# ProteccionesCPLD.net
KiCad netlist of a schematic drawn in Altium Designer
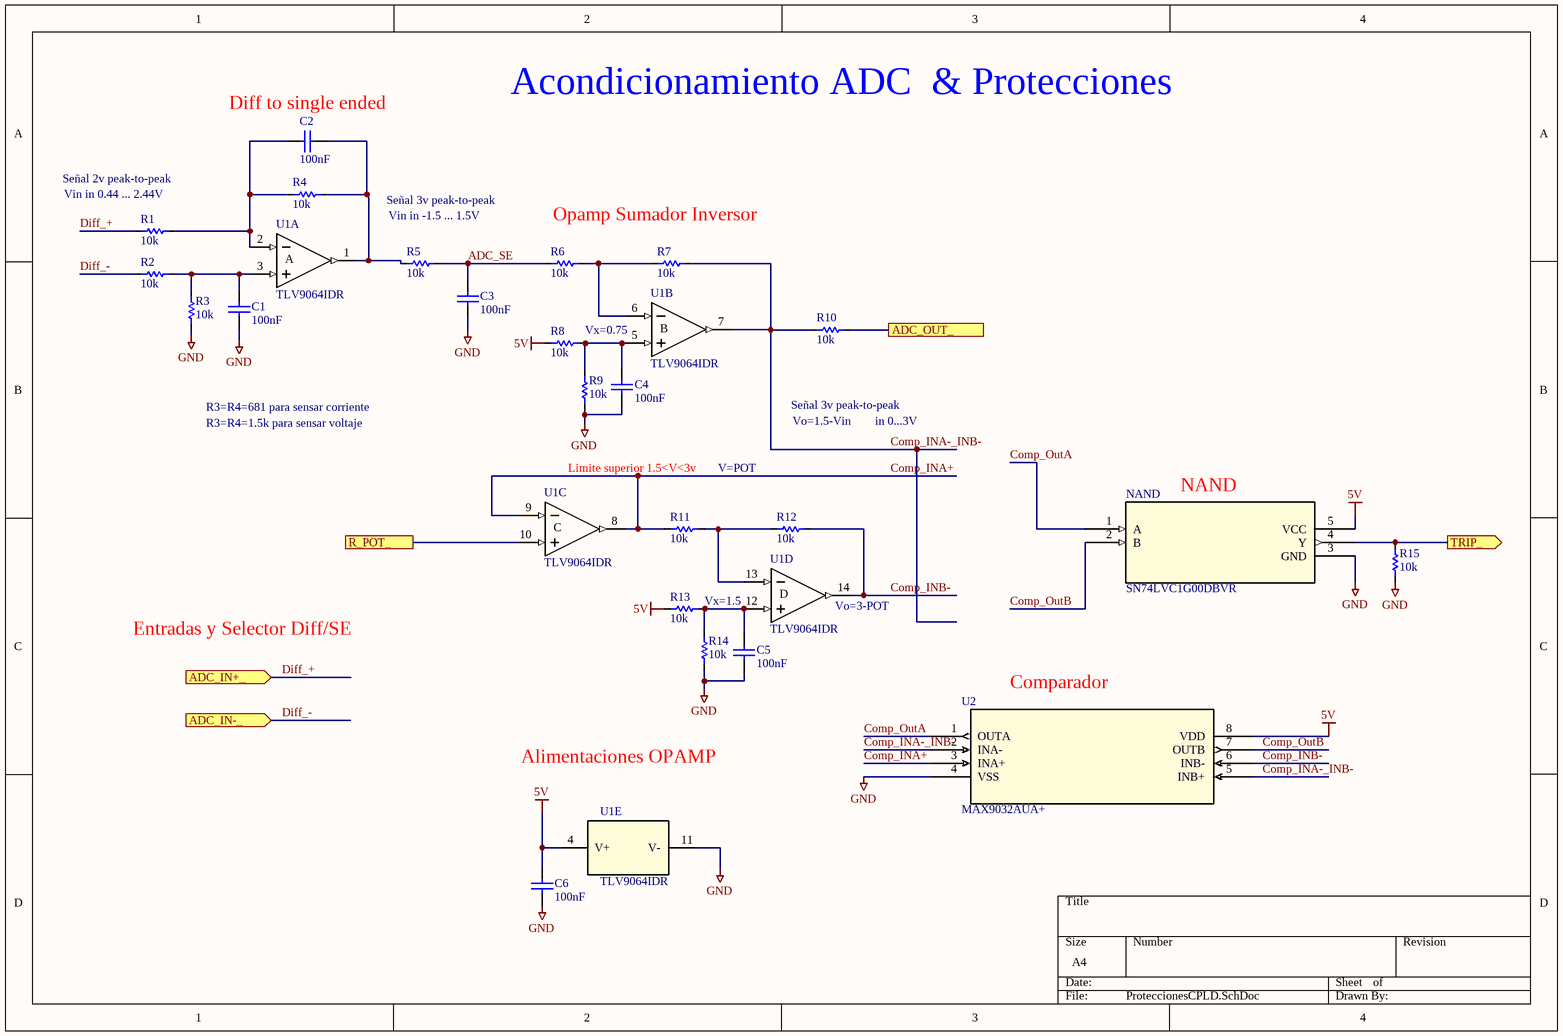
[diagram p0: ProteccionesCPLD.SchDoc]

(export (version "E")
  (design (tool "Eeschema 10.0.6"))
  (components
    (comp (ref "C1")
      (value "100nF")
      (footprint "CAP_0603")
      (description "0.1µF ±10% 50V Ceramic Capacitor X7R 0603 (1608 Metric)")
      (fields (field (name "MF") "KEMET") (field (name "CREATED") "2020_06_15_DAarancibia"))
      (libsource (lib "Schlib1") (part "Cap_0603"))
    )
    (comp (ref "C2")
      (value "100nF")
      (footprint "CAP_0603")
      (description "0.1µF ±10% 50V Ceramic Capacitor X7R 0603 (1608 Metric)")
      (fields (field (name "MF") "KEMET") (field (name "CREATED") "2020_06_15_DAarancibia"))
      (libsource (lib "Schlib1") (part "Cap_0603"))
    )
    (comp (ref "C3")
      (value "100nF")
      (footprint "CAP_0603")
      (description "0.1µF ±10% 50V Ceramic Capacitor X7R 0603 (1608 Metric)")
      (fields (field (name "MF") "KEMET") (field (name "CREATED") "2020_06_15_DAarancibia"))
      (libsource (lib "Schlib1") (part "Cap_0603"))
    )
    (comp (ref "C4")
      (value "100nF")
      (footprint "CAP_0603")
      (description "0.1µF ±10% 50V Ceramic Capacitor X7R 0603 (1608 Metric)")
      (fields (field (name "MF") "KEMET") (field (name "CREATED") "2020_06_15_DAarancibia"))
      (libsource (lib "Schlib1") (part "Cap_0603"))
    )
    (comp (ref "C5")
      (value "100nF")
      (footprint "CAP_0603")
      (description "0.1µF ±10% 50V Ceramic Capacitor X7R 0603 (1608 Metric)")
      (fields (field (name "MF") "KEMET") (field (name "CREATED") "2020_06_15_DAarancibia"))
      (libsource (lib "Schlib1") (part "Cap_0603"))
    )
    (comp (ref "C6")
      (value "100nF")
      (footprint "CAP_0603")
      (description "0.1µF ±10% 50V Ceramic Capacitor X7R 0603 (1608 Metric)")
      (fields (field (name "MF") "KEMET") (field (name "CREATED") "2020_06_15_DAarancibia"))
      (libsource (lib "Schlib1") (part "Cap_0603"))
    )
    (comp (ref "NAND")
      (value "SN74LVC1G00DBVR")
      (footprint "DBV5-M")
      (description "No Description Available")
      (libsource (lib "Schlib1") (part "SN74LVC1G00DBVR"))
    )
    (comp (ref "R1")
      (value "10k")
      (footprint "RES_0603")
      (fields
        (field (name "MF") "Panasonic Electronic Components")
        (field (name "CREATED") "2020_06_15_DAarancibia")
      )
      (libsource (lib "Schlib1") (part "Res_0603"))
    )
    (comp (ref "R2")
      (value "10k")
      (footprint "RES_0603")
      (fields
        (field (name "MF") "Panasonic Electronic Components")
        (field (name "CREATED") "2020_06_15_DAarancibia")
      )
      (libsource (lib "Schlib1") (part "Res_0603"))
    )
    (comp (ref "R3")
      (value "10k")
      (footprint "RES_0603")
      (fields
        (field (name "MF") "Panasonic Electronic Components")
        (field (name "CREATED") "2020_06_15_DAarancibia")
      )
      (libsource (lib "Schlib1") (part "Res_0603"))
    )
    (comp (ref "R4")
      (value "10k")
      (footprint "RES_0603")
      (fields
        (field (name "MF") "Panasonic Electronic Components")
        (field (name "CREATED") "2020_06_15_DAarancibia")
      )
      (libsource (lib "Schlib1") (part "Res_0603"))
    )
    (comp (ref "R5")
      (value "10k")
      (footprint "RES_0603")
      (fields
        (field (name "MF") "Panasonic Electronic Components")
        (field (name "CREATED") "2020_06_15_DAarancibia")
      )
      (libsource (lib "Schlib1") (part "Res_0603"))
    )
    (comp (ref "R6")
      (value "10k")
      (footprint "RES_0603")
      (fields
        (field (name "MF") "Panasonic Electronic Components")
        (field (name "CREATED") "2020_06_15_DAarancibia")
      )
      (libsource (lib "Schlib1") (part "Res_0603"))
    )
    (comp (ref "R7")
      (value "10k")
      (footprint "RES_0603")
      (fields
        (field (name "MF") "Panasonic Electronic Components")
        (field (name "CREATED") "2020_06_15_DAarancibia")
      )
      (libsource (lib "Schlib1") (part "Res_0603"))
    )
    (comp (ref "R8")
      (value "10k")
      (footprint "RES_0603")
      (fields
        (field (name "MF") "Panasonic Electronic Components")
        (field (name "CREATED") "2020_06_15_DAarancibia")
      )
      (libsource (lib "Schlib1") (part "Res_0603"))
    )
    (comp (ref "R9")
      (value "10k")
      (footprint "RES_0603")
      (fields
        (field (name "MF") "Panasonic Electronic Components")
        (field (name "CREATED") "2020_06_15_DAarancibia")
      )
      (libsource (lib "Schlib1") (part "Res_0603"))
    )
    (comp (ref "R10")
      (value "10k")
      (footprint "RES_0603")
      (fields
        (field (name "MF") "Panasonic Electronic Components")
        (field (name "CREATED") "2020_06_15_DAarancibia")
      )
      (libsource (lib "Schlib1") (part "Res_0603"))
    )
    (comp (ref "R11")
      (value "10k")
      (footprint "RES_0603")
      (fields
        (field (name "MF") "Panasonic Electronic Components")
        (field (name "CREATED") "2020_06_15_DAarancibia")
      )
      (libsource (lib "Schlib1") (part "Res_0603"))
    )
    (comp (ref "R12")
      (value "10k")
      (footprint "RES_0603")
      (fields
        (field (name "MF") "Panasonic Electronic Components")
        (field (name "CREATED") "2020_06_15_DAarancibia")
      )
      (libsource (lib "Schlib1") (part "Res_0603"))
    )
    (comp (ref "R13")
      (value "10k")
      (footprint "RES_0603")
      (fields
        (field (name "MF") "Panasonic Electronic Components")
        (field (name "CREATED") "2020_06_15_DAarancibia")
      )
      (libsource (lib "Schlib1") (part "Res_0603"))
    )
    (comp (ref "R14")
      (value "10k")
      (footprint "RES_0603")
      (fields
        (field (name "MF") "Panasonic Electronic Components")
        (field (name "CREATED") "2020_06_15_DAarancibia")
      )
      (libsource (lib "Schlib1") (part "Res_0603"))
    )
    (comp (ref "R15")
      (value "10k")
      (footprint "RES_0603")
      (fields
        (field (name "MF") "Panasonic Electronic Components")
        (field (name "CREATED") "2020_06_15_DAarancibia")
      )
      (libsource (lib "Schlib1") (part "Res_0603"))
    )
    (comp (ref "U1")
      (value "TLV9064IDR")
      (footprint "D0014A_N")
      (description "No Description Available")
      (libsource (lib "Schlib1") (part "TLV9064IDR"))
    )
    (comp (ref "U2")
      (value "MAX9032AUA+")
      (footprint "21-0036K-M")
      (description "No Description Available")
      (libsource (lib "Schlib1") (part "MAX9032AUA+"))
    )
  )
  (nets
    (net (code "1") (name "/ADC_OUT_") (class "Default")
      (node (ref "R10") (pin "1") (pinfunction "1_1") (pintype "passive"))
    )
    (net (code "2") (name "/ADC_SE") (class "Default")
      (node (ref "C3") (pin "1") (pinfunction "1_1") (pintype "passive"))
      (node (ref "R5") (pin "2") (pinfunction "2_2") (pintype "passive"))
      (node (ref "R6") (pin "1") (pinfunction "1_1") (pintype "passive"))
    )
    (net (code "3") (name "/Comp_INA+") (class "Default")
      (node (ref "R11") (pin "1") (pinfunction "1_1") (pintype "passive"))
      (node (ref "U1") (pin "8") (pinfunction "OUT_8") (pintype "output"))
      (node (ref "U1") (pin "9") (pinfunction "IN-_9") (pintype "input"))
      (node (ref "U2") (pin "3") (pinfunction "INA+_3") (pintype "input"))
    )
    (net (code "4") (name "/Comp_INA-_INB-") (class "Default")
      (node (ref "R10") (pin "2") (pinfunction "2_2") (pintype "passive"))
      (node (ref "R7") (pin "1") (pinfunction "1_1") (pintype "passive"))
      (node (ref "U1") (pin "7") (pinfunction "OUT_7") (pintype "output"))
      (node (ref "U2") (pin "2") (pinfunction "INA-_2") (pintype "input"))
      (node (ref "U2") (pin "5") (pinfunction "INB+_5") (pintype "input"))
    )
    (net (code "5") (name "/Comp_INB-") (class "Default")
      (node (ref "R12") (pin "1") (pinfunction "1_1") (pintype "passive"))
      (node (ref "U1") (pin "14") (pinfunction "OUT_14") (pintype "output"))
      (node (ref "U2") (pin "6") (pinfunction "INB-_6") (pintype "input"))
    )
    (net (code "6") (name "/Comp_OutA") (class "Default")
      (node (ref "NAND") (pin "1") (pinfunction "A_1") (pintype "input"))
      (node (ref "U2") (pin "1") (pinfunction "OUTA_1") (pintype "output"))
    )
    (net (code "7") (name "/Comp_OutB") (class "Default")
      (node (ref "NAND") (pin "2") (pinfunction "B_2") (pintype "input"))
      (node (ref "U2") (pin "7") (pinfunction "OUTB_7") (pintype "output"))
    )
    (net (code "8") (name "/Diff_+") (class "Default")
      (node (ref "R1") (pin "1") (pinfunction "1_1") (pintype "passive"))
    )
    (net (code "9") (name "/Diff_-") (class "Default")
      (node (ref "R2") (pin "1") (pinfunction "1_1") (pintype "passive"))
    )
    (net (code "10") (name "/R_POT_") (class "Default")
      (node (ref "U1") (pin "10") (pinfunction "IN+_10") (pintype "input"))
    )
    (net (code "11") (name "/TRIP_") (class "Default")
      (node (ref "NAND") (pin "4") (pinfunction "Y_4") (pintype "output"))
      (node (ref "R15") (pin "2") (pinfunction "2_2") (pintype "passive"))
    )
    (net (code "12") (name "5V") (class "Default")
      (node (ref "C6") (pin "1") (pinfunction "1_1") (pintype "passive"))
      (node (ref "NAND") (pin "5") (pinfunction "VCC_5") (pintype "power_in"))
      (node (ref "R13") (pin "2") (pinfunction "2_2") (pintype "passive"))
      (node (ref "R8") (pin "2") (pinfunction "2_2") (pintype "passive"))
      (node (ref "U1") (pin "4") (pinfunction "V+_4") (pintype "power_in"))
      (node (ref "U2") (pin "8") (pinfunction "VDD_8") (pintype "power_in"))
    )
    (net (code "13") (name "GND") (class "Default")
      (node (ref "C1") (pin "2") (pinfunction "2_2") (pintype "passive"))
      (node (ref "C3") (pin "2") (pinfunction "2_2") (pintype "passive"))
      (node (ref "C4") (pin "2") (pinfunction "2_2") (pintype "passive"))
      (node (ref "C5") (pin "2") (pinfunction "2_2") (pintype "passive"))
      (node (ref "C6") (pin "2") (pinfunction "2_2") (pintype "passive"))
      (node (ref "NAND") (pin "3") (pinfunction "GND_3") (pintype "power_in"))
      (node (ref "R14") (pin "1") (pinfunction "1_1") (pintype "passive"))
      (node (ref "R15") (pin "1") (pinfunction "1_1") (pintype "passive"))
      (node (ref "R3") (pin "2") (pinfunction "2_2") (pintype "passive"))
      (node (ref "R9") (pin "1") (pinfunction "1_1") (pintype "passive"))
      (node (ref "U1") (pin "11") (pinfunction "V-_11") (pintype "power_in"))
      (node (ref "U2") (pin "4") (pinfunction "VSS_4") (pintype "power_in"))
    )
    (net (code "14") (name "Net-(U1A-IN+)") (class "Default")
      (node (ref "C1") (pin "1") (pinfunction "1_1") (pintype "passive"))
      (node (ref "R2") (pin "2") (pinfunction "2_2") (pintype "passive"))
      (node (ref "R3") (pin "1") (pinfunction "1_1") (pintype "passive"))
      (node (ref "U1") (pin "3") (pinfunction "IN+_3") (pintype "input"))
    )
    (net (code "15") (name "Net-(U1A-IN-)") (class "Default")
      (node (ref "C2") (pin "1") (pinfunction "1_1") (pintype "passive"))
      (node (ref "R1") (pin "2") (pinfunction "2_2") (pintype "passive"))
      (node (ref "R4") (pin "1") (pinfunction "1_1") (pintype "passive"))
      (node (ref "U1") (pin "2") (pinfunction "IN-_2") (pintype "input"))
    )
    (net (code "16") (name "Net-(U1A-OUT)") (class "Default")
      (node (ref "C2") (pin "2") (pinfunction "2_2") (pintype "passive"))
      (node (ref "R4") (pin "2") (pinfunction "2_2") (pintype "passive"))
      (node (ref "R5") (pin "1") (pinfunction "1_1") (pintype "passive"))
      (node (ref "U1") (pin "1") (pinfunction "OUT_1") (pintype "output"))
    )
    (net (code "17") (name "Net-(U1B-IN+)") (class "Default")
      (node (ref "C4") (pin "1") (pinfunction "1_1") (pintype "passive"))
      (node (ref "R8") (pin "1") (pinfunction "1_1") (pintype "passive"))
      (node (ref "R9") (pin "2") (pinfunction "2_2") (pintype "passive"))
      (node (ref "U1") (pin "5") (pinfunction "IN+_5") (pintype "input"))
    )
    (net (code "18") (name "Net-(U1B-IN-)") (class "Default")
      (node (ref "R6") (pin "2") (pinfunction "2_2") (pintype "passive"))
      (node (ref "R7") (pin "2") (pinfunction "2_2") (pintype "passive"))
      (node (ref "U1") (pin "6") (pinfunction "IN-_6") (pintype "input"))
    )
    (net (code "19") (name "Net-(U1D-IN+)") (class "Default")
      (node (ref "C5") (pin "1") (pinfunction "1_1") (pintype "passive"))
      (node (ref "R13") (pin "1") (pinfunction "1_1") (pintype "passive"))
      (node (ref "R14") (pin "2") (pinfunction "2_2") (pintype "passive"))
      (node (ref "U1") (pin "12") (pinfunction "IN+_12") (pintype "input"))
    )
    (net (code "20") (name "Net-(U1D-IN-)") (class "Default")
      (node (ref "R11") (pin "2") (pinfunction "2_2") (pintype "passive"))
      (node (ref "R12") (pin "2") (pinfunction "2_2") (pintype "passive"))
      (node (ref "U1") (pin "13") (pinfunction "IN-_13") (pintype "input"))
    )
  )
)
